# VL53L3CX.net
KiCad netlist of a schematic drawn in Altium Designer
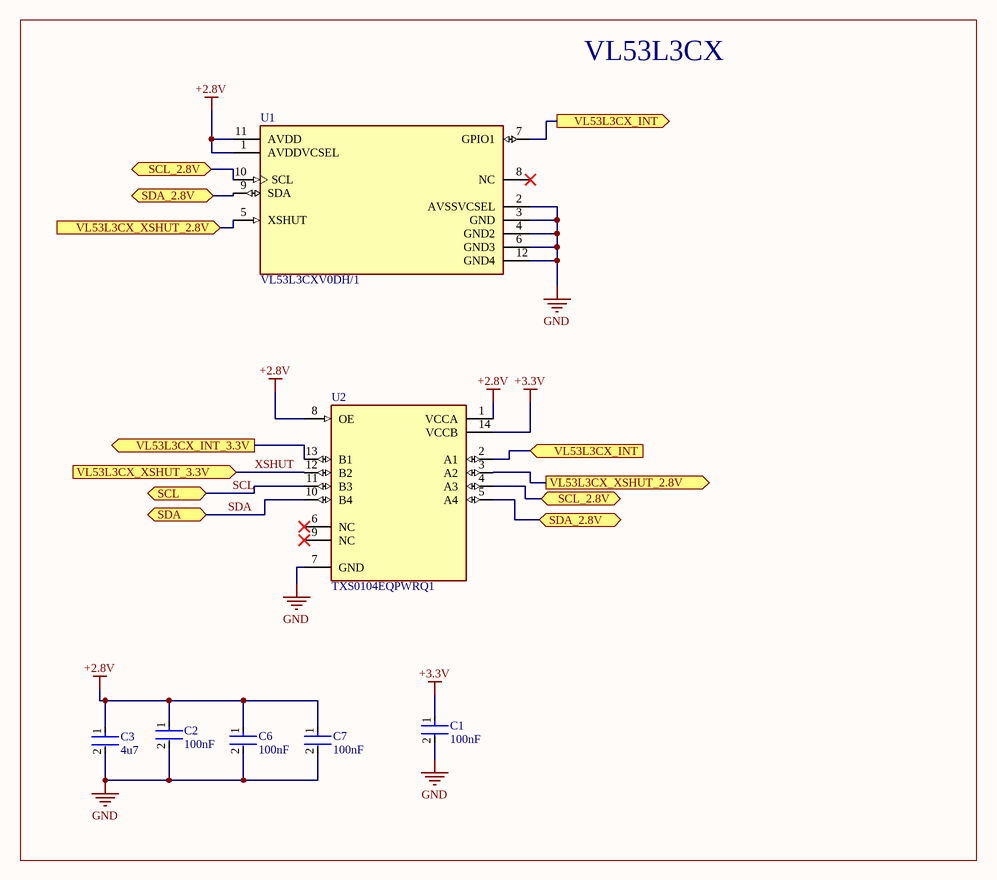
[diagram p0: VL53L3CX.SchDoc]

(export (version "E")
  (design (tool "Eeschema 10.0.6"))
  (components
    (comp (ref "C1")
      (value "100nF")
      (footprint "FP-C1206C-EB-MFG")
      (description "CAP CER 0.1UF 16V 10% X7R 1206")
      (fields (field (name "MANUFACTURER PART NUMBER") "C1206C104K4RACTU") (field (name "TOLERANCE") "0.1"))
      (libsource (lib "Altium Content Vault") (part "b4654b650e69147ec39a6b967a45e02"))
    )
    (comp (ref "C2")
      (value "100nF")
      (footprint "FP-C1206C-EB-MFG")
      (description "CAP CER 0.1UF 16V 10% X7R 1206")
      (fields (field (name "MANUFACTURER PART NUMBER") "C1206C104K4RACTU") (field (name "TOLERANCE") "0.1"))
      (libsource (lib "Altium Content Vault") (part "b4654b650e69147ec39a6b967a45e02"))
    )
    (comp (ref "C3")
      (value "4u7")
      (footprint "FP-GRM21B-0_15-MFG")
      (description "Chip Multilayer Ceramic Capacitors for General Purpose, 0805, 4.7uF, X7R, 15%, 10%, 10V")
      (fields (field (name "TOLERANCE") "10%"))
      (libsource (lib "Altium Content Vault") (part "b4654b650e69147ec39a6b967a45e02"))
    )
    (comp (ref "C6")
      (value "100nF")
      (footprint "FP-C1206C-EB-MFG")
      (description "CAP CER 0.1UF 16V 10% X7R 1206")
      (fields (field (name "MANUFACTURER PART NUMBER") "C1206C104K4RACTU") (field (name "TOLERANCE") "0.1"))
      (libsource (lib "Altium Content Vault") (part "b4654b650e69147ec39a6b967a45e02"))
    )
    (comp (ref "C7")
      (value "100nF")
      (footprint "FP-C1206C-EB-MFG")
      (description "CAP CER 0.1UF 16V 10% X7R 1206")
      (fields (field (name "MANUFACTURER PART NUMBER") "C1206C104K4RACTU") (field (name "TOLERANCE") "0.1"))
      (libsource (lib "Altium Content Vault") (part "b4654b650e69147ec39a6b967a45e02"))
    )
    (comp (ref "U1")
      (value "VL53L3CXV0DH/1")
      (footprint "FP-LGA-12-DM00392521-MFG")
      (description "TIME-OF-FLIGHT PROXIMITY SENSOR")
      (libsource (lib "Altium Content Vault") (part "9713eae9e5ae4921ec4162ad7c400e3"))
    )
    (comp (ref "U2")
      (value "TXS0104EQPWRQ1")
      (footprint "FP-PW0014A-IPC_C")
      (description "IC TRNSLTR BIDIRECTIONAL 14TSSOP")
      (libsource (lib "Altium Content Vault") (part "835088fb1eff5d55cdee0acf0716f10"))
    )
  )
  (nets
    (net (code "1") (name "+2.8V") (class "Default")
      (node (ref "C2") (pin "1") (pinfunction "1_1") (pintype "passive"))
      (node (ref "C3") (pin "1") (pinfunction "1_1") (pintype "passive"))
      (node (ref "C6") (pin "1") (pinfunction "1_1") (pintype "passive"))
      (node (ref "C7") (pin "1") (pinfunction "1_1") (pintype "passive"))
      (node (ref "U1") (pin "1") (pinfunction "AVDDVCSEL_1") (pintype "power_in"))
      (node (ref "U1") (pin "11") (pinfunction "AVDD_11") (pintype "power_in"))
      (node (ref "U2") (pin "1") (pinfunction "VCCA_1") (pintype "power_in"))
      (node (ref "U2") (pin "8") (pinfunction "OE_8") (pintype "input"))
    )
    (net (code "2") (name "+3.3V") (class "Default")
      (node (ref "C1") (pin "1") (pinfunction "1_1") (pintype "passive"))
      (node (ref "U2") (pin "14") (pinfunction "VCCB_14") (pintype "power_in"))
    )
    (net (code "3") (name "/SCL") (class "Default")
      (node (ref "U2") (pin "11") (pinfunction "B3_11") (pintype "bidirectional"))
    )
    (net (code "4") (name "/SCL_2.8V") (class "Default")
      (node (ref "U1") (pin "10") (pinfunction "SCL_10") (pintype "input"))
      (node (ref "U2") (pin "4") (pinfunction "A3_4") (pintype "bidirectional"))
    )
    (net (code "5") (name "/SDA") (class "Default")
      (node (ref "U2") (pin "10") (pinfunction "B4_10") (pintype "bidirectional"))
    )
    (net (code "6") (name "/SDA_2.8V") (class "Default")
      (node (ref "U1") (pin "9") (pinfunction "SDA_9") (pintype "bidirectional"))
      (node (ref "U2") (pin "5") (pinfunction "A4_5") (pintype "bidirectional"))
    )
    (net (code "7") (name "/VL53L3CX_INT") (class "Default")
      (node (ref "U1") (pin "7") (pinfunction "GPIO1_7") (pintype "bidirectional"))
      (node (ref "U2") (pin "2") (pinfunction "A1_2") (pintype "bidirectional"))
    )
    (net (code "8") (name "/VL53L3CX_INT_3.3V") (class "Default")
      (node (ref "U2") (pin "13") (pinfunction "B1_13") (pintype "bidirectional"))
    )
    (net (code "9") (name "/VL53L3CX_XSHUT_2.8V") (class "Default")
      (node (ref "U1") (pin "5") (pinfunction "XSHUT_5") (pintype "input"))
      (node (ref "U2") (pin "3") (pinfunction "A2_3") (pintype "bidirectional"))
    )
    (net (code "10") (name "/XSHUT") (class "Default")
      (node (ref "U2") (pin "12") (pinfunction "B2_12") (pintype "bidirectional"))
    )
    (net (code "11") (name "GND") (class "Default")
      (node (ref "C1") (pin "2") (pinfunction "2_2") (pintype "passive"))
      (node (ref "C2") (pin "2") (pinfunction "2_2") (pintype "passive"))
      (node (ref "C3") (pin "2") (pinfunction "2_2") (pintype "passive"))
      (node (ref "C6") (pin "2") (pinfunction "2_2") (pintype "passive"))
      (node (ref "C7") (pin "2") (pinfunction "2_2") (pintype "passive"))
      (node (ref "U1") (pin "12") (pinfunction "GND4_12") (pintype "power_in"))
      (node (ref "U1") (pin "2") (pinfunction "AVSSVCSEL_2") (pintype "power_in"))
      (node (ref "U1") (pin "3") (pinfunction "GND_3") (pintype "power_in"))
      (node (ref "U1") (pin "4") (pinfunction "GND2_4") (pintype "power_in"))
      (node (ref "U1") (pin "6") (pinfunction "GND3_6") (pintype "power_in"))
      (node (ref "U2") (pin "7") (pinfunction "GND_7") (pintype "power_in"))
    )
    (net (code "12") (name "unconnected-(U1-NC-Pad8)") (class "Default")
      (node (ref "U1") (pin "8") (pinfunction "NC_8") (pintype "passive+no_connect"))
    )
    (net (code "13") (name "unconnected-(U2-NC-Pad6)") (class "Default")
      (node (ref "U2") (pin "6") (pinfunction "NC_6") (pintype "passive+no_connect"))
    )
    (net (code "14") (name "unconnected-(U2-NC-Pad9)") (class "Default")
      (node (ref "U2") (pin "9") (pinfunction "NC_9") (pintype "passive+no_connect"))
    )
  )
)
